# PCI_trifasico.net
KiCad netlist of a schematic drawn in EasyEDA Pro
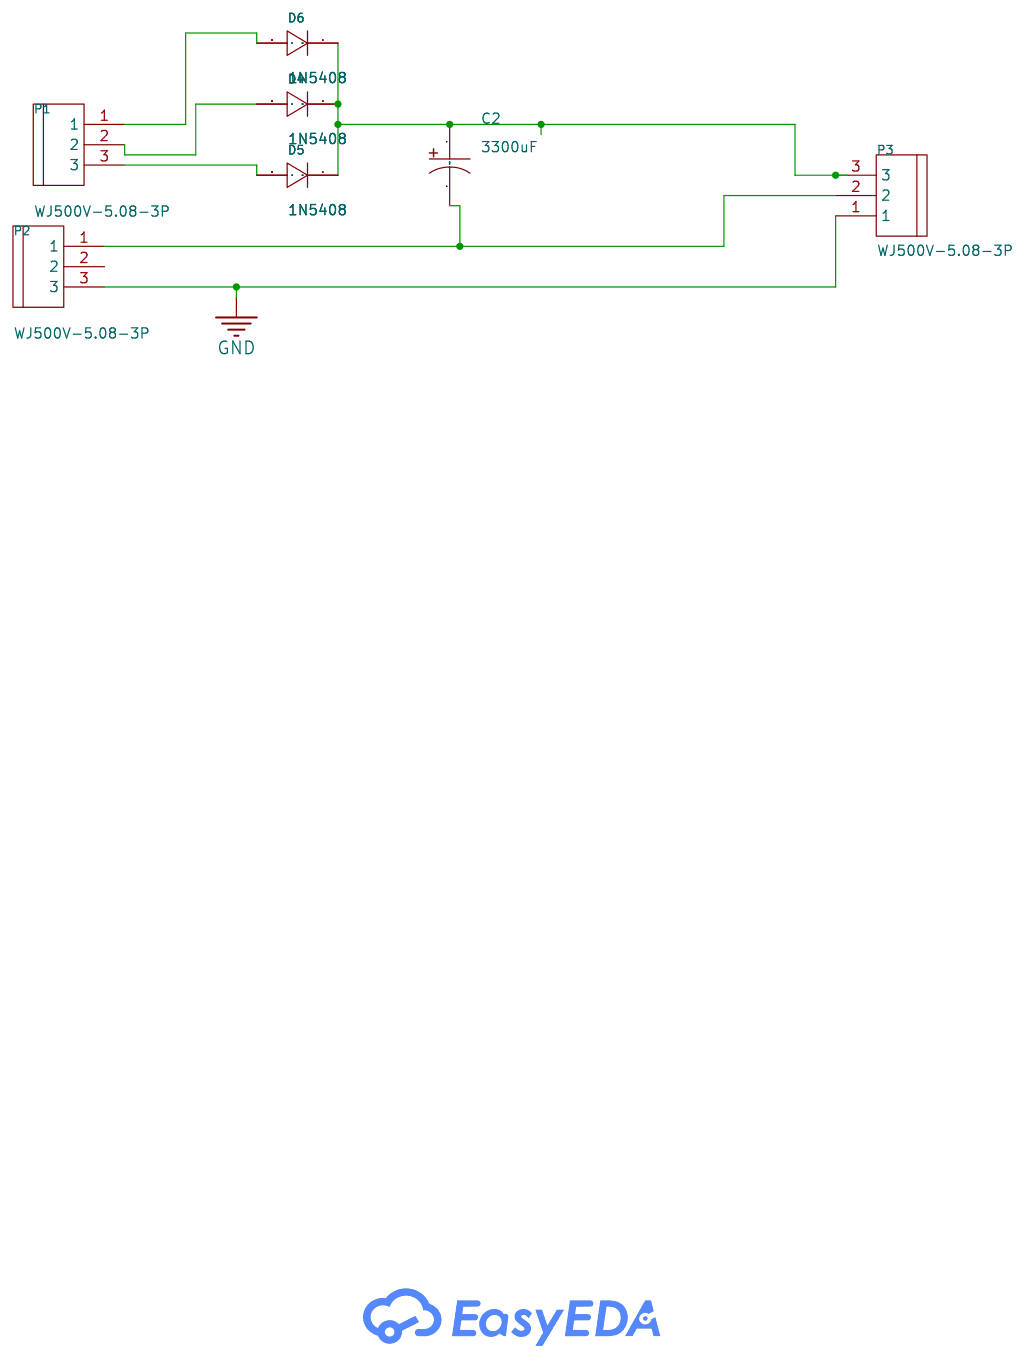
[diagram p0: schematic sheet]

(export (version "E")
  (design (tool "Eeschema 10.0.6"))
  (components
    (comp (ref "C2")
      (value "3300uF")
      (footprint "easyedapro:CAP-TH_BD40.0-P10.00-D2.3-FD")
      (fields
        (field (name "Manufacturer Part") "RP2G561MT350S68CE0")
        (field (name "Manufacturer") "HUAWEI(华威集团)")
      )
      (libsource (lib "easyedapro") (part "RP2G561MT350S68CE0"))
    )
    (comp (ref "D4")
      (value "1N5408")
      (footprint "easyedapro:DO-201_BD5.3-L9.5-P13.50-D1.4-RD")
      (fields (field (name "Manufacturer") "LRC(乐山无线电)"))
      (libsource (lib "easyedapro") (part "1N5408-C82807"))
    )
    (comp (ref "D5")
      (value "1N5408")
      (footprint "easyedapro:DO-201_BD5.3-L9.5-P13.50-D1.4-RD")
      (fields (field (name "Manufacturer") "LRC(乐山无线电)"))
      (libsource (lib "easyedapro") (part "1N5408-C82807"))
    )
    (comp (ref "D6")
      (value "1N5408")
      (footprint "easyedapro:DO-201_BD5.3-L9.5-P13.50-D1.4-RD")
      (fields (field (name "Manufacturer") "LRC(乐山无线电)"))
      (libsource (lib "easyedapro") (part "1N5408-C82807"))
    )
    (comp (ref "P1")
      (value "WJ500V-5.08-3P")
      (footprint "easyedapro:CONN-TH_3P-P5.00_WJ500V-5.08-3P")
      (fields (field (name "Manufacturer") "KANGNEX(康奈克斯电气)"))
      (libsource (lib "easyedapro") (part "WJ500V-5.08-3P-14-00A"))
    )
    (comp (ref "P2")
      (value "WJ500V-5.08-3P")
      (footprint "easyedapro:CONN-TH_3P-P5.00_WJ500V-5.08-3P")
      (fields (field (name "Manufacturer") "KANGNEX(康奈克斯电气)"))
      (libsource (lib "easyedapro") (part "WJ500V-5.08-3P-14-00A"))
    )
    (comp (ref "P3")
      (value "WJ500V-5.08-3P")
      (footprint "easyedapro:CONN-TH_3P-P5.00_WJ500V-5.08-3P")
      (fields (field (name "Manufacturer") "KANGNEX(康奈克斯电气)"))
      (libsource (lib "easyedapro") (part "WJ500V-5.08-3P-14-00A"))
    )
  )
  (nets
    (net (code "1") (name "GND") (class "Default")
      (node (ref "P2") (pin "3") (pinfunction "3_3") (pintype "input"))
      (node (ref "P3") (pin "1") (pinfunction "1_1") (pintype "input"))
    )
    (net (code "2") (name "Net-(C2-Pad2)") (class "Default")
      (node (ref "C2") (pin "2") (pinfunction "2_2") (pintype "input"))
      (node (ref "P2") (pin "1") (pinfunction "1_1") (pintype "input"))
      (node (ref "P3") (pin "2") (pinfunction "2_2") (pintype "input"))
    )
    (net (code "3") (name "Net-(D4-A)") (class "Default")
      (node (ref "D4") (pin "2") (pinfunction "A_2") (pintype "input"))
      (node (ref "P1") (pin "2") (pinfunction "2_2") (pintype "input"))
    )
    (net (code "4") (name "Net-(D4-C)") (class "Default")
      (node (ref "C2") (pin "1") (pinfunction "1_1") (pintype "input"))
      (node (ref "D4") (pin "1") (pinfunction "C_1") (pintype "input"))
      (node (ref "D5") (pin "1") (pinfunction "C_1") (pintype "input"))
      (node (ref "D6") (pin "1") (pinfunction "C_1") (pintype "input"))
      (node (ref "P3") (pin "3") (pinfunction "3_3") (pintype "input"))
    )
    (net (code "5") (name "Net-(D5-A)") (class "Default")
      (node (ref "D5") (pin "2") (pinfunction "A_2") (pintype "input"))
      (node (ref "P1") (pin "3") (pinfunction "3_3") (pintype "input"))
    )
    (net (code "6") (name "Net-(D6-A)") (class "Default")
      (node (ref "D6") (pin "2") (pinfunction "A_2") (pintype "input"))
      (node (ref "P1") (pin "1") (pinfunction "1_1") (pintype "input"))
    )
    (net (code "7") (name "unconnected-(P2-Pad2)") (class "Default")
      (node (ref "P2") (pin "2") (pinfunction "2_2") (pintype "input"))
    )
  )
)
